# Flat_Back_Eurorack_Busboard.net
KiCad netlist of a schematic drawn in EAGLE
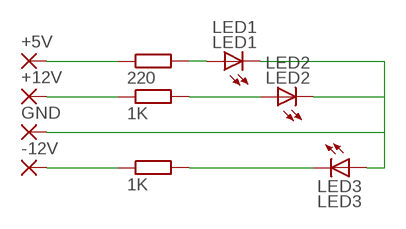
[diagram p0: schematic, sheet 1]

(export (version "E")
  (design (tool "Eeschema 10.0.6"))
  (components
    (comp (ref "+5V")
      (value "SMD5")
      (footprint "eagle-import:SMD2,54-5,08")
      (libsource (lib "eagle-import") (part "SMD5"))
    )
    (comp (ref "+12V")
      (value "SMD5")
      (footprint "eagle-import:SMD2,54-5,08")
      (libsource (lib "eagle-import") (part "SMD5"))
    )
    (comp (ref "-12V")
      (value "SMD5")
      (footprint "eagle-import:SMD2,54-5,08")
      (libsource (lib "eagle-import") (part "SMD5"))
    )
    (comp (ref "GND")
      (value "SMD5")
      (footprint "eagle-import:SMD2,54-5,08")
      (libsource (lib "eagle-import") (part "SMD5"))
    )
    (comp (ref "LED1")
      (value "LED1")
      (footprint "eagle-import:CHIPLED_0805")
      (libsource (lib "eagle-import") (part "LEDCHIPLED_0805"))
    )
    (comp (ref "LED2")
      (value "LED2")
      (footprint "eagle-import:CHIPLED_0805")
      (libsource (lib "eagle-import") (part "LEDCHIPLED_0805"))
    )
    (comp (ref "LED3")
      (value "LED3")
      (footprint "eagle-import:CHIPLED_0805")
      (libsource (lib "eagle-import") (part "LEDCHIPLED_0805"))
    )
    (comp (ref "R1")
      (value "220")
      (footprint "eagle-import:M0805")
      (libsource (lib "eagle-import") (part "R-EU_M0805"))
    )
    (comp (ref "R2")
      (value "1K")
      (footprint "eagle-import:M0805")
      (libsource (lib "eagle-import") (part "R-EU_M0805"))
    )
    (comp (ref "R3")
      (value "1K")
      (footprint "eagle-import:M0805")
      (libsource (lib "eagle-import") (part "R-EU_M0805"))
    )
  )
  (nets
    (net (code "1") (name "Net-(+5V-P)") (class "Default")
      (node (ref "+5V") (pin "1") (pinfunction "P_1") (pintype "passive"))
      (node (ref "R1") (pin "1") (pinfunction "1_1") (pintype "passive"))
    )
    (net (code "2") (name "Net-(+12V-P)") (class "Default")
      (node (ref "+12V") (pin "1") (pinfunction "P_1") (pintype "passive"))
      (node (ref "R2") (pin "1") (pinfunction "1_1") (pintype "passive"))
    )
    (net (code "3") (name "Net-(-12V-P)") (class "Default")
      (node (ref "-12V") (pin "1") (pinfunction "P_1") (pintype "passive"))
      (node (ref "R3") (pin "1") (pinfunction "1_1") (pintype "passive"))
    )
    (net (code "4") (name "Net-(GND-P)") (class "Default")
      (node (ref "GND") (pin "1") (pinfunction "P_1") (pintype "passive"))
      (node (ref "LED1") (pin "C") (pinfunction "C_C") (pintype "passive"))
      (node (ref "LED2") (pin "C") (pinfunction "C_C") (pintype "passive"))
      (node (ref "LED3") (pin "A") (pinfunction "A_A") (pintype "passive"))
    )
    (net (code "5") (name "Net-(LED1-PadA)") (class "Default")
      (node (ref "LED1") (pin "A") (pinfunction "A_A") (pintype "passive"))
      (node (ref "R1") (pin "2") (pinfunction "2_2") (pintype "passive"))
    )
    (net (code "6") (name "Net-(LED2-PadA)") (class "Default")
      (node (ref "LED2") (pin "A") (pinfunction "A_A") (pintype "passive"))
      (node (ref "R2") (pin "2") (pinfunction "2_2") (pintype "passive"))
    )
    (net (code "7") (name "Net-(LED3-PadC)") (class "Default")
      (node (ref "LED3") (pin "C") (pinfunction "C_C") (pintype "passive"))
      (node (ref "R3") (pin "2") (pinfunction "2_2") (pintype "passive"))
    )
  )
)
